# Brians_test_board_1_16.net
KiCad netlist of a schematic drawn in EAGLE
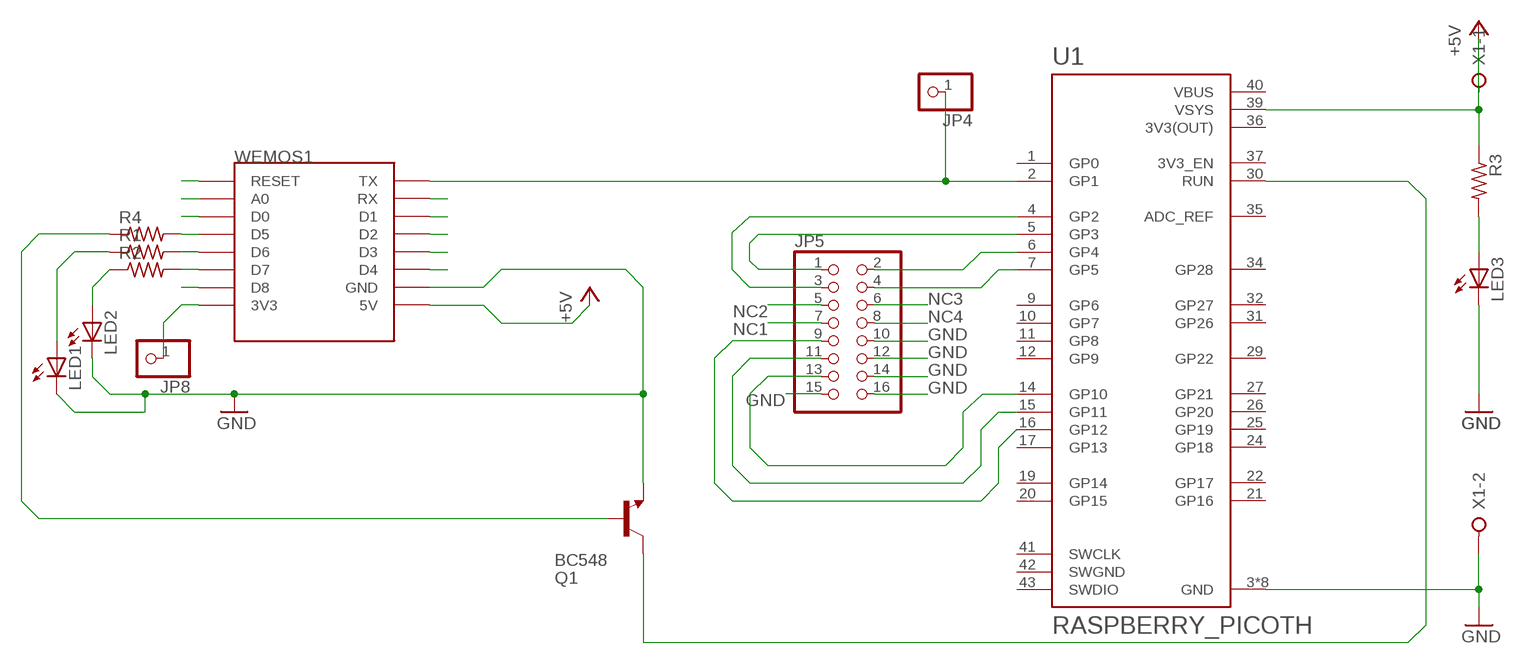
[diagram p0: schematic, sheet 1]

(export (version "E")
  (design (tool "Eeschema 10.0.6"))
  (components
    (comp (ref "JP4")
      (value "PINHD-1X1")
      (footprint "eagle-import:1X01")
      (libsource (lib "eagle-import") (part "PINHD-1X1"))
    )
    (comp (ref "JP5")
      (value "PINHD-2X8")
      (footprint "eagle-import:2X08")
      (libsource (lib "eagle-import") (part "PINHD-2X8"))
    )
    (comp (ref "JP8")
      (value "PINHD-1X1")
      (footprint "eagle-import:1X01")
      (libsource (lib "eagle-import") (part "PINHD-1X1"))
    )
    (comp (ref "LED1")
      (value "LED3MM")
      (footprint "eagle-import:LED3MM")
      (libsource (lib "eagle-import") (part "LED3MM"))
    )
    (comp (ref "LED2")
      (value "LED3MM")
      (footprint "eagle-import:LED3MM")
      (libsource (lib "eagle-import") (part "LED3MM"))
    )
    (comp (ref "LED3")
      (value "LED3MM")
      (footprint "eagle-import:LED3MM")
      (libsource (lib "eagle-import") (part "LED3MM"))
    )
    (comp (ref "Q1")
      (value "BC548")
      (footprint "eagle-import:TO92-EBC")
      (libsource (lib "eagle-import") (part "BC548"))
    )
    (comp (ref "R1")
      (value "R-US_0204/2V")
      (footprint "eagle-import:0204V")
      (libsource (lib "eagle-import") (part "R-US_0204/2V"))
    )
    (comp (ref "R2")
      (value "R-US_0204/2V")
      (footprint "eagle-import:0204V")
      (libsource (lib "eagle-import") (part "R-US_0204/2V"))
    )
    (comp (ref "R3")
      (value "R-US_0207/10")
      (footprint "eagle-import:0207_10")
      (libsource (lib "eagle-import") (part "R-US_0207/10"))
    )
    (comp (ref "R4")
      (value "R-US_0204/2V")
      (footprint "eagle-import:0204V")
      (libsource (lib "eagle-import") (part "R-US_0204/2V"))
    )
    (comp (ref "U1")
      (value "RASPBERRY_PICOTH")
      (footprint "eagle-import:PICO-PKG-TH")
      (libsource (lib "eagle-import") (part "RASPBERRY_PICOTH"))
    )
    (comp (ref "WEMOS1")
      (value "WEMOS-D1-MINI")
      (footprint "eagle-import:WEMOS-D1-MINI")
      (libsource (lib "eagle-import") (part "WEMOS-D1-MINI"))
    )
    (comp (ref "X1")
      (value "W237-02P")
      (footprint "eagle-import:W237-132")
      (libsource (lib "eagle-import") (part "W237-02P"))
    )
  )
  (nets
    (net (code "1") (name "+5V") (class "Default")
      (node (ref "R3") (pin "1") (pinfunction "1_1") (pintype "passive"))
      (node (ref "U1") (pin "39") (pinfunction "VSYS_39") (pintype "power_in"))
      (node (ref "WEMOS1") (pin "5V") (pinfunction "5V_5V") (pintype "bidirectional"))
      (node (ref "X1") (pin "1") (pinfunction "KL_1") (pintype "passive"))
    )
    (net (code "2") (name "/3V3(OUT)") (class "Default")
      (node (ref "U1") (pin "36") (pinfunction "3V3(OUT)_36") (pintype "power_in"))
    )
    (net (code "3") (name "/NC1") (class "Default")
      (node (ref "JP5") (pin "7") (pinfunction "7_7") (pintype "passive"))
    )
    (net (code "4") (name "/NC2") (class "Default")
      (node (ref "JP5") (pin "5") (pinfunction "5_5") (pintype "passive"))
    )
    (net (code "5") (name "/NC3") (class "Default")
      (node (ref "JP5") (pin "6") (pinfunction "6_6") (pintype "passive"))
    )
    (net (code "6") (name "/NC4") (class "Default")
      (node (ref "JP5") (pin "8") (pinfunction "8_8") (pintype "passive"))
    )
    (net (code "7") (name "/SWGND") (class "Default")
      (node (ref "U1") (pin "42") (pinfunction "SWGND_42") (pintype "power_in"))
    )
    (net (code "8") (name "/VBUS") (class "Default")
      (node (ref "U1") (pin "40") (pinfunction "VBUS_40") (pintype "power_in"))
    )
    (net (code "9") (name "GND") (class "Default")
      (node (ref "JP5") (pin "10") (pinfunction "10_10") (pintype "passive"))
      (node (ref "JP5") (pin "12") (pinfunction "12_12") (pintype "passive"))
      (node (ref "JP5") (pin "14") (pinfunction "14_14") (pintype "passive"))
      (node (ref "JP5") (pin "15") (pinfunction "15_15") (pintype "passive"))
      (node (ref "JP5") (pin "16") (pinfunction "16_16") (pintype "passive"))
      (node (ref "LED1") (pin "K") (pinfunction "C_K") (pintype "passive"))
      (node (ref "LED2") (pin "K") (pinfunction "C_K") (pintype "passive"))
      (node (ref "LED3") (pin "K") (pinfunction "C_K") (pintype "passive"))
      (node (ref "Q1") (pin "E") (pinfunction "E_E") (pintype "passive"))
      (node (ref "U1") (pin "13") (pinfunction "GND_13") (pintype "power_in"))
      (node (ref "U1") (pin "18") (pinfunction "GND_18") (pintype "power_in"))
      (node (ref "U1") (pin "23") (pinfunction "GND_23") (pintype "power_in"))
      (node (ref "U1") (pin "28") (pinfunction "GND_28") (pintype "power_in"))
      (node (ref "U1") (pin "3") (pinfunction "GND_3") (pintype "power_in"))
      (node (ref "U1") (pin "33") (pinfunction "GND_33") (pintype "power_in"))
      (node (ref "U1") (pin "38") (pinfunction "GND_38") (pintype "power_in"))
      (node (ref "U1") (pin "8") (pinfunction "GND_8") (pintype "power_in"))
      (node (ref "WEMOS1") (pin "GND") (pinfunction "GND_GND") (pintype "bidirectional"))
      (node (ref "X1") (pin "2") (pinfunction "KL_2") (pintype "passive"))
    )
    (net (code "10") (name "Net-(JP8-Pad1)") (class "Default")
      (node (ref "JP8") (pin "1") (pinfunction "1_1") (pintype "passive"))
      (node (ref "WEMOS1") (pin "3V3") (pinfunction "3V3_3V3") (pintype "bidirectional"))
    )
    (net (code "11") (name "Net-(LED1-PadA)") (class "Default")
      (node (ref "LED1") (pin "A") (pinfunction "A_A") (pintype "passive"))
      (node (ref "R1") (pin "1") (pinfunction "1_1") (pintype "passive"))
    )
    (net (code "12") (name "Net-(LED2-PadA)") (class "Default")
      (node (ref "LED2") (pin "A") (pinfunction "A_A") (pintype "passive"))
      (node (ref "R2") (pin "1") (pinfunction "1_1") (pintype "passive"))
    )
    (net (code "13") (name "Net-(LED3-PadA)") (class "Default")
      (node (ref "LED3") (pin "A") (pinfunction "A_A") (pintype "passive"))
      (node (ref "R3") (pin "2") (pinfunction "2_2") (pintype "passive"))
    )
    (net (code "14") (name "Net-(Q1-PadB)") (class "Default")
      (node (ref "Q1") (pin "B") (pinfunction "B_B") (pintype "passive"))
      (node (ref "R4") (pin "1") (pinfunction "1_1") (pintype "passive"))
    )
    (net (code "15") (name "Net-(R1-Pad2)") (class "Default")
      (node (ref "R1") (pin "2") (pinfunction "2_2") (pintype "passive"))
      (node (ref "WEMOS1") (pin "D6") (pinfunction "D6_D6") (pintype "bidirectional"))
    )
    (net (code "16") (name "Net-(R2-Pad2)") (class "Default")
      (node (ref "R2") (pin "2") (pinfunction "2_2") (pintype "passive"))
      (node (ref "WEMOS1") (pin "D7") (pinfunction "D7_D7") (pintype "bidirectional"))
    )
    (net (code "17") (name "Net-(R4-Pad2)") (class "Default")
      (node (ref "R4") (pin "2") (pinfunction "2_2") (pintype "passive"))
      (node (ref "WEMOS1") (pin "D5") (pinfunction "D5_D5") (pintype "bidirectional"))
    )
    (net (code "18") (name "Net-(U1-GP1)") (class "Default")
      (node (ref "JP4") (pin "1") (pinfunction "1_1") (pintype "passive"))
      (node (ref "U1") (pin "2") (pinfunction "GP1_2") (pintype "bidirectional"))
      (node (ref "WEMOS1") (pin "TX") (pinfunction "TX_TX") (pintype "bidirectional"))
    )
    (net (code "19") (name "Net-(U1-GP2)") (class "Default")
      (node (ref "JP5") (pin "3") (pinfunction "3_3") (pintype "passive"))
      (node (ref "U1") (pin "4") (pinfunction "GP2_4") (pintype "bidirectional"))
    )
    (net (code "20") (name "Net-(U1-GP3)") (class "Default")
      (node (ref "JP5") (pin "1") (pinfunction "1_1") (pintype "passive"))
      (node (ref "U1") (pin "5") (pinfunction "GP3_5") (pintype "bidirectional"))
    )
    (net (code "21") (name "Net-(U1-GP4)") (class "Default")
      (node (ref "JP5") (pin "2") (pinfunction "2_2") (pintype "passive"))
      (node (ref "U1") (pin "6") (pinfunction "GP4_6") (pintype "bidirectional"))
    )
    (net (code "22") (name "Net-(U1-GP5)") (class "Default")
      (node (ref "JP5") (pin "4") (pinfunction "4_4") (pintype "passive"))
      (node (ref "U1") (pin "7") (pinfunction "GP5_7") (pintype "bidirectional"))
    )
    (net (code "23") (name "Net-(U1-GP10)") (class "Default")
      (node (ref "JP5") (pin "13") (pinfunction "13_13") (pintype "passive"))
      (node (ref "U1") (pin "14") (pinfunction "GP10_14") (pintype "bidirectional"))
    )
    (net (code "24") (name "Net-(U1-GP11)") (class "Default")
      (node (ref "JP5") (pin "11") (pinfunction "11_11") (pintype "passive"))
      (node (ref "U1") (pin "15") (pinfunction "GP11_15") (pintype "bidirectional"))
    )
    (net (code "25") (name "Net-(U1-GP12)") (class "Default")
      (node (ref "JP5") (pin "9") (pinfunction "9_9") (pintype "passive"))
      (node (ref "U1") (pin "16") (pinfunction "GP12_16") (pintype "bidirectional"))
    )
    (net (code "26") (name "Net-(U1-RUN)") (class "Default")
      (node (ref "Q1") (pin "C") (pinfunction "C_C") (pintype "passive"))
      (node (ref "U1") (pin "30") (pinfunction "RUN_30") (pintype "input"))
    )
    (net (code "27") (name "unconnected-(U1-3V3_EN-Pad37)") (class "Default")
      (node (ref "U1") (pin "37") (pinfunction "3V3_EN_37") (pintype "input"))
    )
    (net (code "28") (name "unconnected-(U1-ADC_REF-Pad35)") (class "Default")
      (node (ref "U1") (pin "35") (pinfunction "ADC_REF_35") (pintype "input"))
    )
    (net (code "29") (name "unconnected-(U1-GP0-Pad1)") (class "Default")
      (node (ref "U1") (pin "1") (pinfunction "GP0_1") (pintype "bidirectional"))
    )
    (net (code "30") (name "unconnected-(U1-GP6-Pad9)") (class "Default")
      (node (ref "U1") (pin "9") (pinfunction "GP6_9") (pintype "bidirectional"))
    )
    (net (code "31") (name "unconnected-(U1-GP7-Pad10)") (class "Default")
      (node (ref "U1") (pin "10") (pinfunction "GP7_10") (pintype "bidirectional"))
    )
    (net (code "32") (name "unconnected-(U1-GP8-Pad11)") (class "Default")
      (node (ref "U1") (pin "11") (pinfunction "GP8_11") (pintype "bidirectional"))
    )
    (net (code "33") (name "unconnected-(U1-GP9-Pad12)") (class "Default")
      (node (ref "U1") (pin "12") (pinfunction "GP9_12") (pintype "bidirectional"))
    )
    (net (code "34") (name "unconnected-(U1-GP13-Pad17)") (class "Default")
      (node (ref "U1") (pin "17") (pinfunction "GP13_17") (pintype "bidirectional"))
    )
    (net (code "35") (name "unconnected-(U1-GP14-Pad19)") (class "Default")
      (node (ref "U1") (pin "19") (pinfunction "GP14_19") (pintype "bidirectional"))
    )
    (net (code "36") (name "unconnected-(U1-GP15-Pad20)") (class "Default")
      (node (ref "U1") (pin "20") (pinfunction "GP15_20") (pintype "bidirectional"))
    )
    (net (code "37") (name "unconnected-(U1-GP16-Pad21)") (class "Default")
      (node (ref "U1") (pin "21") (pinfunction "GP16_21") (pintype "bidirectional"))
    )
    (net (code "38") (name "unconnected-(U1-GP17-Pad22)") (class "Default")
      (node (ref "U1") (pin "22") (pinfunction "GP17_22") (pintype "bidirectional"))
    )
    (net (code "39") (name "unconnected-(U1-GP18-Pad24)") (class "Default")
      (node (ref "U1") (pin "24") (pinfunction "GP18_24") (pintype "bidirectional"))
    )
    (net (code "40") (name "unconnected-(U1-GP19-Pad25)") (class "Default")
      (node (ref "U1") (pin "25") (pinfunction "GP19_25") (pintype "bidirectional"))
    )
    (net (code "41") (name "unconnected-(U1-GP20-Pad26)") (class "Default")
      (node (ref "U1") (pin "26") (pinfunction "GP20_26") (pintype "bidirectional"))
    )
    (net (code "42") (name "unconnected-(U1-GP21-Pad27)") (class "Default")
      (node (ref "U1") (pin "27") (pinfunction "GP21_27") (pintype "bidirectional"))
    )
    (net (code "43") (name "unconnected-(U1-GP22-Pad29)") (class "Default")
      (node (ref "U1") (pin "29") (pinfunction "GP22_29") (pintype "bidirectional"))
    )
    (net (code "44") (name "unconnected-(U1-GP26-Pad31)") (class "Default")
      (node (ref "U1") (pin "31") (pinfunction "GP26_31") (pintype "bidirectional"))
    )
    (net (code "45") (name "unconnected-(U1-GP27-Pad32)") (class "Default")
      (node (ref "U1") (pin "32") (pinfunction "GP27_32") (pintype "bidirectional"))
    )
    (net (code "46") (name "unconnected-(U1-GP28-Pad34)") (class "Default")
      (node (ref "U1") (pin "34") (pinfunction "GP28_34") (pintype "bidirectional"))
    )
    (net (code "47") (name "unconnected-(U1-SWCLK-Pad41)") (class "Default")
      (node (ref "U1") (pin "41") (pinfunction "SWCLK_41") (pintype "input"))
    )
    (net (code "48") (name "unconnected-(U1-SWDIO-Pad43)") (class "Default")
      (node (ref "U1") (pin "43") (pinfunction "SWDIO_43") (pintype "bidirectional"))
    )
    (net (code "49") (name "unconnected-(WEMOS1-PadA0)") (class "Default")
      (node (ref "WEMOS1") (pin "A0") (pinfunction "A0_A0") (pintype "bidirectional"))
    )
    (net (code "50") (name "unconnected-(WEMOS1-PadD0)") (class "Default")
      (node (ref "WEMOS1") (pin "D0") (pinfunction "D0_D0") (pintype "bidirectional"))
    )
    (net (code "51") (name "unconnected-(WEMOS1-PadD1)") (class "Default")
      (node (ref "WEMOS1") (pin "D1") (pinfunction "D1_D1") (pintype "bidirectional"))
    )
    (net (code "52") (name "unconnected-(WEMOS1-PadD2)") (class "Default")
      (node (ref "WEMOS1") (pin "D2") (pinfunction "D2_D2") (pintype "bidirectional"))
    )
    (net (code "53") (name "unconnected-(WEMOS1-PadD3)") (class "Default")
      (node (ref "WEMOS1") (pin "D3") (pinfunction "D3_D3") (pintype "bidirectional"))
    )
    (net (code "54") (name "unconnected-(WEMOS1-PadD4)") (class "Default")
      (node (ref "WEMOS1") (pin "D4") (pinfunction "D4_D4") (pintype "bidirectional"))
    )
    (net (code "55") (name "unconnected-(WEMOS1-PadD8)") (class "Default")
      (node (ref "WEMOS1") (pin "D8") (pinfunction "D8_D8") (pintype "bidirectional"))
    )
    (net (code "56") (name "unconnected-(WEMOS1-PadRESET)") (class "Default")
      (node (ref "WEMOS1") (pin "RESET") (pinfunction "RESET_RESET") (pintype "bidirectional"))
    )
    (net (code "57") (name "unconnected-(WEMOS1-PadRX)") (class "Default")
      (node (ref "WEMOS1") (pin "RX") (pinfunction "RX_RX") (pintype "bidirectional"))
    )
  )
)
